# Op-Amp_Clock_Generator.net
KiCad netlist of a schematic drawn in EAGLE
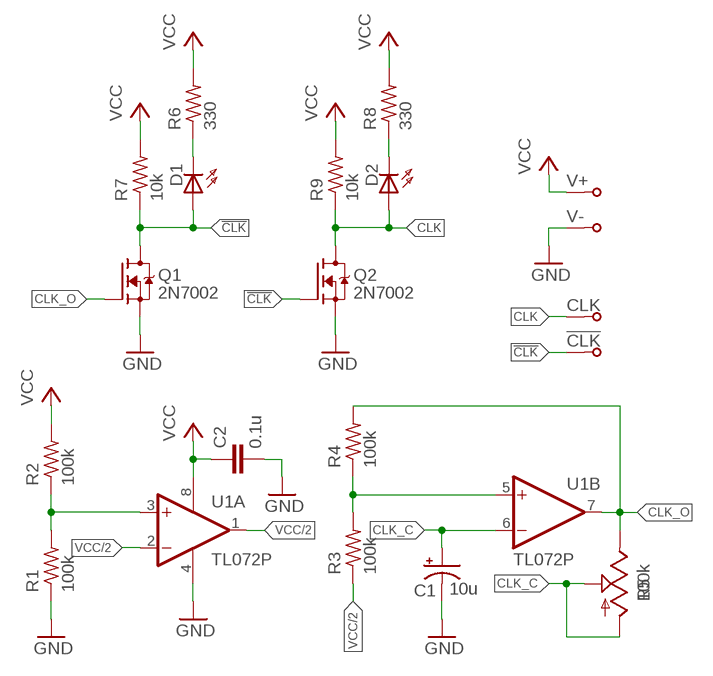
[diagram p0: schematic, sheet 1]

(export (version "E")
  (design (tool "Eeschema 10.0.6"))
  (components
    (comp (ref "!CLK")
      (value "TPTHT")
      (footprint "eagle-import:PROTOPAD-THT-PAD")
      (libsource (lib "eagle-import") (part "TPTHT"))
    )
    (comp (ref "C1")
      (value "10u")
      (footprint "eagle-import:TT2D5")
      (libsource (lib "eagle-import") (part "CAP_POLLYTIC_V"))
    )
    (comp (ref "C2")
      (value "0.1u")
      (footprint "eagle-import:C0603")
      (libsource (lib "eagle-import") (part "CAP0603"))
    )
    (comp (ref "CLK")
      (value "TPTHT")
      (footprint "eagle-import:PROTOPAD-THT-PAD")
      (libsource (lib "eagle-import") (part "TPTHT"))
    )
    (comp (ref "D1")
      (value "LED0603")
      (footprint "eagle-import:CHIP-LED0603")
      (libsource (lib "eagle-import") (part "LED0603"))
    )
    (comp (ref "D2")
      (value "LED0603")
      (footprint "eagle-import:CHIP-LED0603")
      (libsource (lib "eagle-import") (part "LED0603"))
    )
    (comp (ref "Q1")
      (value "2N7002")
      (footprint "eagle-import:SOT23")
      (libsource (lib "eagle-import") (part "2N7002"))
    )
    (comp (ref "Q2")
      (value "2N7002")
      (footprint "eagle-import:SOT23")
      (libsource (lib "eagle-import") (part "2N7002"))
    )
    (comp (ref "R1")
      (value "100k")
      (footprint "eagle-import:R0603")
      (libsource (lib "eagle-import") (part "RES0603"))
    )
    (comp (ref "R2")
      (value "100k")
      (footprint "eagle-import:R0603")
      (libsource (lib "eagle-import") (part "RES0603"))
    )
    (comp (ref "R3")
      (value "100k")
      (footprint "eagle-import:R0603")
      (libsource (lib "eagle-import") (part "RES0603"))
    )
    (comp (ref "R4")
      (value "100k")
      (footprint "eagle-import:R0603")
      (libsource (lib "eagle-import") (part "RES0603"))
    )
    (comp (ref "R5")
      (value "100k")
      (footprint "eagle-import:ALPHA_POT_VERTICAL")
      (libsource (lib "eagle-import") (part "ALPHA_POT_VERTICALVERTICAL"))
    )
    (comp (ref "R6")
      (value "330")
      (footprint "eagle-import:R0603")
      (libsource (lib "eagle-import") (part "RES0603"))
    )
    (comp (ref "R7")
      (value "10k")
      (footprint "eagle-import:R0603")
      (libsource (lib "eagle-import") (part "RES0603"))
    )
    (comp (ref "R8")
      (value "330")
      (footprint "eagle-import:R0603")
      (libsource (lib "eagle-import") (part "RES0603"))
    )
    (comp (ref "R9")
      (value "10k")
      (footprint "eagle-import:R0603")
      (libsource (lib "eagle-import") (part "RES0603"))
    )
    (comp (ref "U1")
      (value "TL072P")
      (footprint "eagle-import:DIL08")
      (libsource (lib "eagle-import") (part "TL072P"))
    )
    (comp (ref "V+")
      (value "TPTHT")
      (footprint "eagle-import:PROTOPAD-THT-PAD")
      (libsource (lib "eagle-import") (part "TPTHT"))
    )
    (comp (ref "V-")
      (value "TPTHT")
      (footprint "eagle-import:PROTOPAD-THT-PAD")
      (libsource (lib "eagle-import") (part "TPTHT"))
    )
  )
  (nets
    (net (code "1") (name "/~{CLK}") (class "Default")
      (node (ref "!CLK") (pin "P1") (pinfunction "S_P1") (pintype "passive"))
      (node (ref "D1") (pin "A") (pinfunction "A_A") (pintype "passive"))
      (node (ref "Q1") (pin "3") (pinfunction "D_3") (pintype "passive"))
      (node (ref "Q2") (pin "1") (pinfunction "G_1") (pintype "passive"))
      (node (ref "R7") (pin "1") (pinfunction "1_1") (pintype "passive"))
    )
    (net (code "2") (name "CLK") (class "Default")
      (node (ref "CLK") (pin "P1") (pinfunction "S_P1") (pintype "passive"))
      (node (ref "D2") (pin "A") (pinfunction "A_A") (pintype "passive"))
      (node (ref "Q2") (pin "3") (pinfunction "D_3") (pintype "passive"))
      (node (ref "R9") (pin "1") (pinfunction "1_1") (pintype "passive"))
    )
    (net (code "3") (name "CLK_C") (class "Default")
      (node (ref "C1") (pin "+") (pinfunction "+_+") (pintype "passive"))
      (node (ref "R5") (pin "P$2") (pinfunction "S_P$2") (pintype "passive"))
      (node (ref "R5") (pin "P$3") (pinfunction "A_P$3") (pintype "passive"))
      (node (ref "U1") (pin "6") (pinfunction "-IN_6") (pintype "input"))
    )
    (net (code "4") (name "CLK_O") (class "Default")
      (node (ref "Q1") (pin "1") (pinfunction "G_1") (pintype "passive"))
      (node (ref "R4") (pin "2") (pinfunction "2_2") (pintype "passive"))
      (node (ref "R5") (pin "P$1") (pinfunction "E_P$1") (pintype "passive"))
      (node (ref "U1") (pin "7") (pinfunction "OUT_7") (pintype "output"))
    )
    (net (code "5") (name "GND") (class "Default")
      (node (ref "C1") (pin "-") (pinfunction "-_-") (pintype "passive"))
      (node (ref "C2") (pin "2") (pinfunction "2_2") (pintype "passive"))
      (node (ref "Q1") (pin "2") (pinfunction "S_2") (pintype "passive"))
      (node (ref "Q2") (pin "2") (pinfunction "S_2") (pintype "passive"))
      (node (ref "R1") (pin "1") (pinfunction "1_1") (pintype "passive"))
      (node (ref "U1") (pin "4") (pinfunction "V-_4") (pintype "power_in"))
      (node (ref "V-") (pin "P1") (pinfunction "S_P1") (pintype "passive"))
    )
    (net (code "6") (name "Net-(D1-K)") (class "Default")
      (node (ref "D1") (pin "C") (pinfunction "K_C") (pintype "passive"))
      (node (ref "R6") (pin "1") (pinfunction "1_1") (pintype "passive"))
    )
    (net (code "7") (name "Net-(D2-K)") (class "Default")
      (node (ref "D2") (pin "C") (pinfunction "K_C") (pintype "passive"))
      (node (ref "R8") (pin "1") (pinfunction "1_1") (pintype "passive"))
    )
    (net (code "8") (name "Net-(U1A-+IN)") (class "Default")
      (node (ref "R1") (pin "2") (pinfunction "2_2") (pintype "passive"))
      (node (ref "R2") (pin "1") (pinfunction "1_1") (pintype "passive"))
      (node (ref "U1") (pin "3") (pinfunction "+IN_3") (pintype "input"))
    )
    (net (code "9") (name "Net-(U1B-+IN)") (class "Default")
      (node (ref "R3") (pin "2") (pinfunction "2_2") (pintype "passive"))
      (node (ref "R4") (pin "1") (pinfunction "1_1") (pintype "passive"))
      (node (ref "U1") (pin "5") (pinfunction "+IN_5") (pintype "input"))
    )
    (net (code "10") (name "VCC") (class "Default")
      (node (ref "C2") (pin "1") (pinfunction "1_1") (pintype "passive"))
      (node (ref "R2") (pin "2") (pinfunction "2_2") (pintype "passive"))
      (node (ref "R6") (pin "2") (pinfunction "2_2") (pintype "passive"))
      (node (ref "R7") (pin "2") (pinfunction "2_2") (pintype "passive"))
      (node (ref "R8") (pin "2") (pinfunction "2_2") (pintype "passive"))
      (node (ref "R9") (pin "2") (pinfunction "2_2") (pintype "passive"))
      (node (ref "U1") (pin "8") (pinfunction "V+_8") (pintype "power_in"))
      (node (ref "V+") (pin "P1") (pinfunction "S_P1") (pintype "passive"))
    )
    (net (code "11") (name "VCC{slash}2") (class "Default")
      (node (ref "R3") (pin "1") (pinfunction "1_1") (pintype "passive"))
      (node (ref "U1") (pin "1") (pinfunction "OUT_1") (pintype "output"))
      (node (ref "U1") (pin "2") (pinfunction "-IN_2") (pintype "input"))
    )
  )
)
